# 34064-test-board.net
KiCad netlist of a schematic drawn in EAGLE
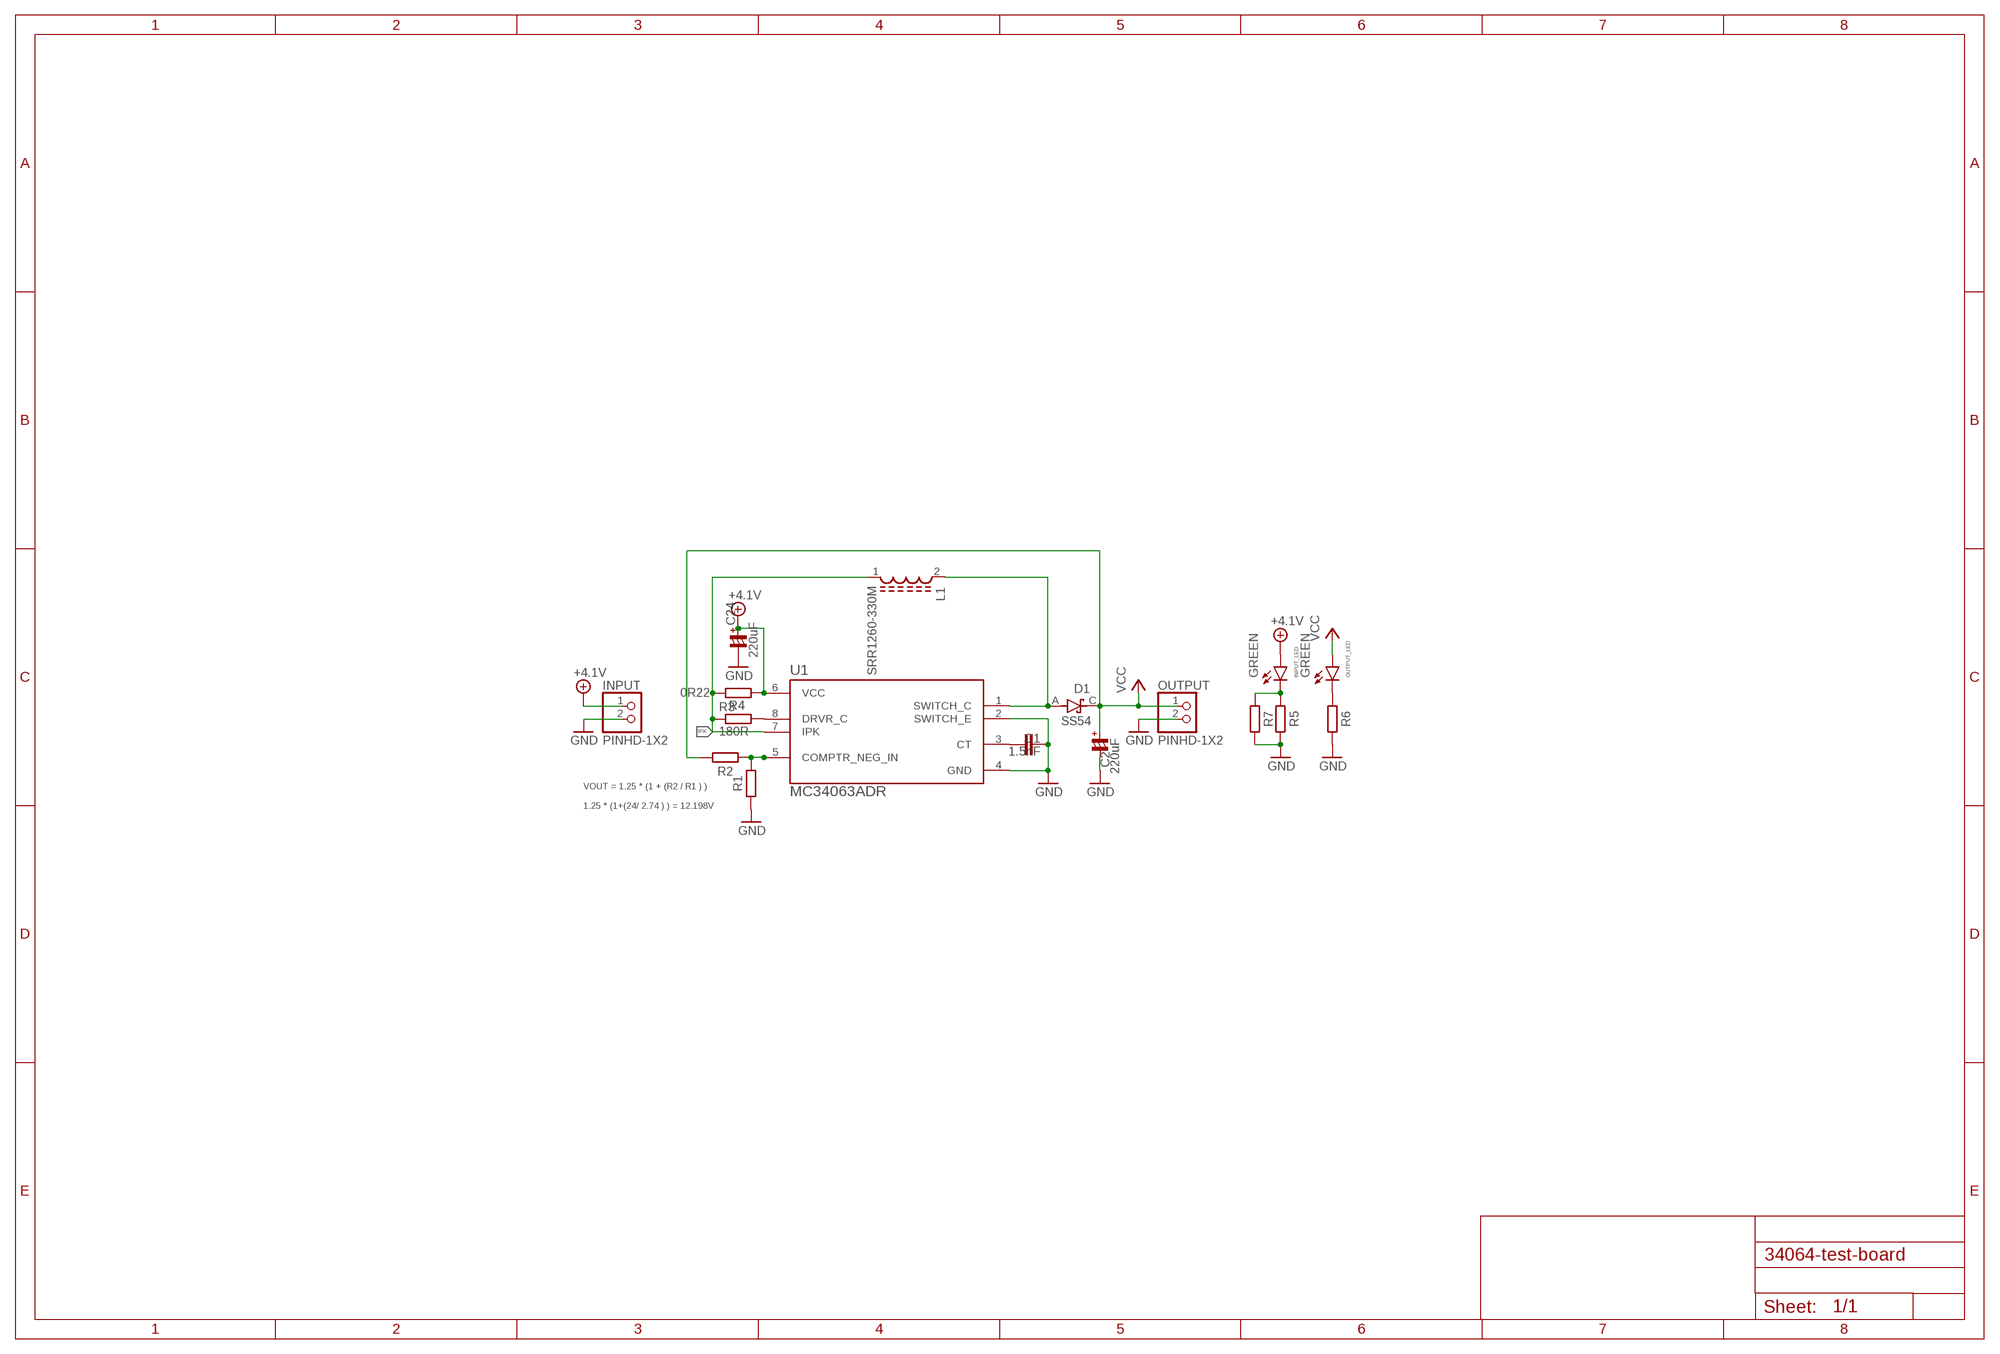
[diagram p0: schematic, sheet 1]

(export (version "E")
  (design (tool "Eeschema 10.0.6"))
  (components
    (comp (ref "C1")
      (value "1.5nF")
      (footprint "eagle-import:C0603")
      (libsource (lib "eagle-import") (part "C-EUC0603"))
    )
    (comp (ref "C2")
      (value "220uF")
      (footprint "eagle-import:RC-MASTER-SMD_C7343-43")
      (libsource (lib "eagle-import") (part "RC-MASTER-SMD_CP_7343-43"))
    )
    (comp (ref "C24")
      (value "220uF")
      (footprint "eagle-import:RC-MASTER-SMD_C7343-43")
      (libsource (lib "eagle-import") (part "RC-MASTER-SMD_CP_7343-43"))
    )
    (comp (ref "D1")
      (value "SS54")
      (footprint "eagle-import:DIOM5336X265N")
      (fields (field (name "MF") "ON Semiconductor") (field (name "MP") "SS24"))
      (libsource (lib "eagle-import") (part "SS54"))
    )
    (comp (ref "INPUT")
      (value "PINHD-1X2")
      (footprint "eagle-import:1X02")
      (libsource (lib "eagle-import") (part "PINHD-1X2"))
    )
    (comp (ref "INPUT_LED")
      (value "GREEN")
      (footprint "eagle-import:CHIPLED_0603")
      (libsource (lib "eagle-import") (part "LEDCHIPLED_0603"))
    )
    (comp (ref "L1")
      (value "SRR1260-330M")
      (footprint "eagle-import:INDP125125X600N")
      (fields (field (name "MF") "Bourns"))
      (libsource (lib "eagle-import") (part "SRR1260-330M"))
    )
    (comp (ref "OUTPUT")
      (value "PINHD-1X2")
      (footprint "eagle-import:1X02")
      (libsource (lib "eagle-import") (part "PINHD-1X2"))
    )
    (comp (ref "OUTPUT_LED")
      (value "GREEN")
      (footprint "eagle-import:CHIPLED_0603")
      (libsource (lib "eagle-import") (part "LEDCHIPLED_0603"))
    )
    (comp (ref "R1")
      (value "2K2")
      (footprint "eagle-import:R0402")
      (libsource (lib "eagle-import") (part "resistors-scott_37623644_R-EU_R0402"))
    )
    (comp (ref "R2")
      (value "20K")
      (footprint "eagle-import:R0402")
      (libsource (lib "eagle-import") (part "resistors-scott_37623644_R-EU_R0402"))
    )
    (comp (ref "R3")
      (value "180R")
      (footprint "eagle-import:R0603")
      (libsource (lib "eagle-import") (part "resistors-scott_37623644_R-EU_R0603"))
    )
    (comp (ref "R4")
      (value "0R22")
      (footprint "eagle-import:R0805")
      (libsource (lib "eagle-import") (part "R-EU_R0805"))
    )
    (comp (ref "R5")
      (value "2K74")
      (footprint "eagle-import:R0402")
      (libsource (lib "eagle-import") (part "resistors-scott_37623644_R-EU_R0402"))
    )
    (comp (ref "R6")
      (value "2K74")
      (footprint "eagle-import:R0402")
      (libsource (lib "eagle-import") (part "resistors-scott_37623644_R-EU_R0402"))
    )
    (comp (ref "R7")
      (value "2K74")
      (footprint "eagle-import:R0402")
      (libsource (lib "eagle-import") (part "resistors-scott_37623644_R-EU_R0402"))
    )
    (comp (ref "U1")
      (value "MC34063ADR")
      (footprint "eagle-import:SOIC127P599X175-8N")
      (fields (field (name "MF") "Texas Instruments"))
      (libsource (lib "eagle-import") (part "MC34063ADR"))
    )
  )
  (nets
    (net (code "1") (name "+4.1V") (class "Default")
      (node (ref "C24") (pin "+") (pinfunction "+_+") (pintype "passive"))
      (node (ref "INPUT") (pin "1") (pinfunction "1_1") (pintype "passive"))
      (node (ref "INPUT_LED") (pin "A") (pinfunction "A_A") (pintype "passive"))
      (node (ref "R4") (pin "2") (pinfunction "2_2") (pintype "passive"))
      (node (ref "U1") (pin "6") (pinfunction "VCC_6") (pintype "power_in"))
    )
    (net (code "2") (name "GND") (class "Default")
      (node (ref "C1") (pin "2") (pinfunction "2_2") (pintype "passive"))
      (node (ref "C2") (pin "-") (pinfunction "-_-") (pintype "passive"))
      (node (ref "C24") (pin "-") (pinfunction "-_-") (pintype "passive"))
      (node (ref "INPUT") (pin "2") (pinfunction "2_2") (pintype "passive"))
      (node (ref "OUTPUT") (pin "2") (pinfunction "2_2") (pintype "passive"))
      (node (ref "R1") (pin "2") (pinfunction "2_2") (pintype "passive"))
      (node (ref "R5") (pin "1") (pinfunction "1_1") (pintype "passive"))
      (node (ref "R6") (pin "1") (pinfunction "1_1") (pintype "passive"))
      (node (ref "R7") (pin "1") (pinfunction "1_1") (pintype "passive"))
      (node (ref "U1") (pin "2") (pinfunction "SWITCH_E_2") (pintype "bidirectional"))
      (node (ref "U1") (pin "4") (pinfunction "GND_4") (pintype "power_in"))
    )
    (net (code "3") (name "IPK") (class "Default")
      (node (ref "L1") (pin "1") (pinfunction "1_1") (pintype "passive"))
      (node (ref "R3") (pin "1") (pinfunction "1_1") (pintype "passive"))
      (node (ref "R4") (pin "1") (pinfunction "1_1") (pintype "passive"))
      (node (ref "U1") (pin "7") (pinfunction "IPK_7") (pintype "input"))
    )
    (net (code "4") (name "Net-(INPUT_LED-PadC)") (class "Default")
      (node (ref "INPUT_LED") (pin "C") (pinfunction "C_C") (pintype "passive"))
      (node (ref "R5") (pin "2") (pinfunction "2_2") (pintype "passive"))
      (node (ref "R7") (pin "2") (pinfunction "2_2") (pintype "passive"))
    )
    (net (code "5") (name "Net-(OUTPUT_LED-PadC)") (class "Default")
      (node (ref "OUTPUT_LED") (pin "C") (pinfunction "C_C") (pintype "passive"))
      (node (ref "R6") (pin "2") (pinfunction "2_2") (pintype "passive"))
    )
    (net (code "6") (name "Net-(U1-COMPTR_NEG_IN)") (class "Default")
      (node (ref "R1") (pin "1") (pinfunction "1_1") (pintype "passive"))
      (node (ref "R2") (pin "2") (pinfunction "2_2") (pintype "passive"))
      (node (ref "U1") (pin "5") (pinfunction "COMPTR_NEG_IN_5") (pintype "input"))
    )
    (net (code "7") (name "Net-(U1-CT)") (class "Default")
      (node (ref "C1") (pin "1") (pinfunction "1_1") (pintype "passive"))
      (node (ref "U1") (pin "3") (pinfunction "CT_3") (pintype "passive"))
    )
    (net (code "8") (name "Net-(U1-DRVR_C)") (class "Default")
      (node (ref "R3") (pin "2") (pinfunction "2_2") (pintype "passive"))
      (node (ref "U1") (pin "8") (pinfunction "DRVR_C_8") (pintype "bidirectional"))
    )
    (net (code "9") (name "Net-(U1-SWITCH_C)") (class "Default")
      (node (ref "D1") (pin "A") (pinfunction "A_A") (pintype "passive"))
      (node (ref "L1") (pin "2") (pinfunction "2_2") (pintype "passive"))
      (node (ref "U1") (pin "1") (pinfunction "SWITCH_C_1") (pintype "bidirectional"))
    )
    (net (code "10") (name "VCC") (class "Default")
      (node (ref "C2") (pin "+") (pinfunction "+_+") (pintype "passive"))
      (node (ref "D1") (pin "C") (pinfunction "K_C") (pintype "passive"))
      (node (ref "OUTPUT") (pin "1") (pinfunction "1_1") (pintype "passive"))
      (node (ref "OUTPUT_LED") (pin "A") (pinfunction "A_A") (pintype "passive"))
      (node (ref "R2") (pin "1") (pinfunction "1_1") (pintype "passive"))
    )
  )
)
